# fonte-tensao-ajustavel.net
KiCad netlist of a schematic drawn in EAGLE
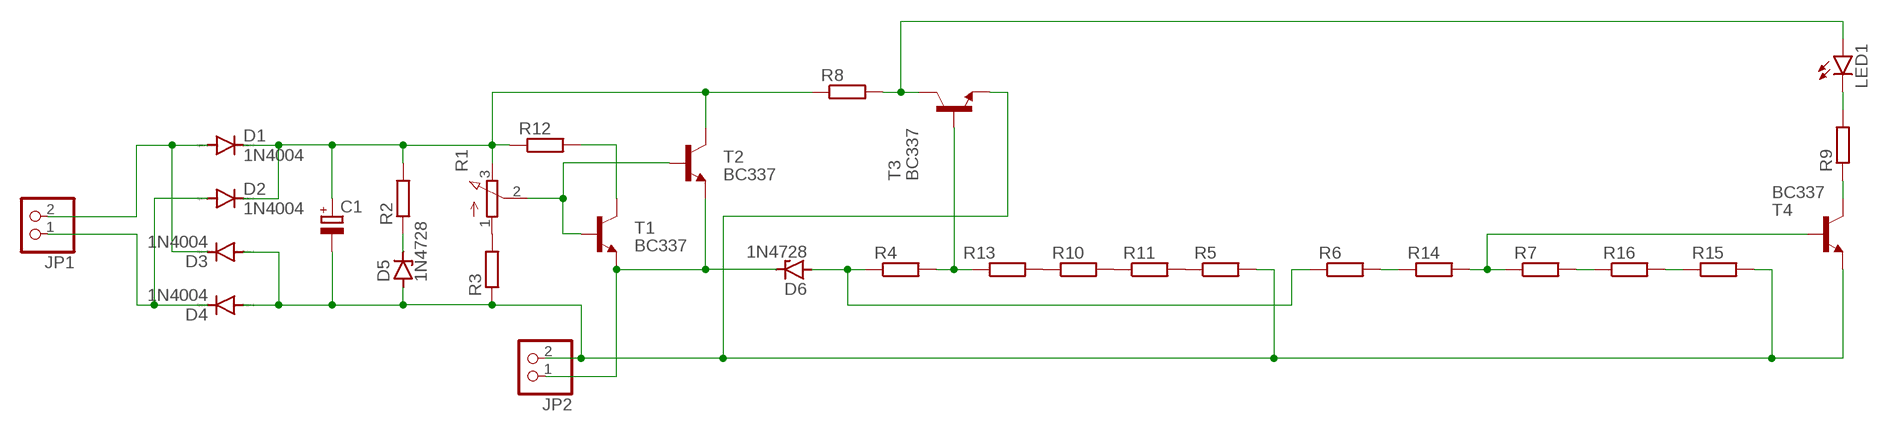
[diagram p0: schematic, sheet 1]

(export (version "E")
  (design (tool "Eeschema 10.0.6"))
  (components
    (comp (ref "C1")
      (value "CPOL-EUE5-10.5")
      (footprint "eagle-import:E5-10,5")
      (libsource (lib "eagle-import") (part "CPOL-EUE5-10.5"))
    )
    (comp (ref "D1")
      (value "1N4004")
      (footprint "eagle-import:DO41-10")
      (libsource (lib "eagle-import") (part "1N4004"))
    )
    (comp (ref "D2")
      (value "1N4004")
      (footprint "eagle-import:DO41-10")
      (libsource (lib "eagle-import") (part "1N4004"))
    )
    (comp (ref "D3")
      (value "1N4004")
      (footprint "eagle-import:DO41-10")
      (libsource (lib "eagle-import") (part "1N4004"))
    )
    (comp (ref "D4")
      (value "1N4004")
      (footprint "eagle-import:DO41-10")
      (libsource (lib "eagle-import") (part "1N4004"))
    )
    (comp (ref "D5")
      (value "1N4728")
      (footprint "eagle-import:DO41Z10")
      (libsource (lib "eagle-import") (part "1N4728"))
    )
    (comp (ref "D6")
      (value "1N4728")
      (footprint "eagle-import:DO41Z10")
      (libsource (lib "eagle-import") (part "1N4728"))
    )
    (comp (ref "JP1")
      (value "PINHD-1X2")
      (footprint "eagle-import:1X02")
      (libsource (lib "eagle-import") (part "PINHD-1X2"))
    )
    (comp (ref "JP2")
      (value "PINHD-1X2")
      (footprint "eagle-import:1X02")
      (libsource (lib "eagle-import") (part "PINHD-1X2"))
    )
    (comp (ref "LED1")
      (value "LED5MM")
      (footprint "eagle-import:LED5MM")
      (libsource (lib "eagle-import") (part "LED5MM"))
    )
    (comp (ref "R1")
      (value "3RP/1610N")
      (footprint "eagle-import:3RP_1610N")
      (libsource (lib "eagle-import") (part "3RP/1610N"))
    )
    (comp (ref "R2")
      (value "R-EU_0204/7")
      (footprint "eagle-import:0204_7")
      (libsource (lib "eagle-import") (part "R-EU_0204/7"))
    )
    (comp (ref "R3")
      (value "R-EU_0204/7")
      (footprint "eagle-import:0204_7")
      (libsource (lib "eagle-import") (part "R-EU_0204/7"))
    )
    (comp (ref "R4")
      (value "R-EU_0204/7")
      (footprint "eagle-import:0204_7")
      (libsource (lib "eagle-import") (part "R-EU_0204/7"))
    )
    (comp (ref "R5")
      (value "R-EU_0204/7")
      (footprint "eagle-import:0204_7")
      (libsource (lib "eagle-import") (part "R-EU_0204/7"))
    )
    (comp (ref "R6")
      (value "R-EU_0204/7")
      (footprint "eagle-import:0204_7")
      (libsource (lib "eagle-import") (part "R-EU_0204/7"))
    )
    (comp (ref "R7")
      (value "R-EU_0204/7")
      (footprint "eagle-import:0204_7")
      (libsource (lib "eagle-import") (part "R-EU_0204/7"))
    )
    (comp (ref "R8")
      (value "R-EU_0204/7")
      (footprint "eagle-import:0204_7")
      (libsource (lib "eagle-import") (part "R-EU_0204/7"))
    )
    (comp (ref "R9")
      (value "R-EU_0204/7")
      (footprint "eagle-import:0204_7")
      (libsource (lib "eagle-import") (part "R-EU_0204/7"))
    )
    (comp (ref "R10")
      (value "R-EU_0204/7")
      (footprint "eagle-import:0204_7")
      (libsource (lib "eagle-import") (part "R-EU_0204/7"))
    )
    (comp (ref "R11")
      (value "R-EU_0204/7")
      (footprint "eagle-import:0204_7")
      (libsource (lib "eagle-import") (part "R-EU_0204/7"))
    )
    (comp (ref "R12")
      (value "R-EU_0414/15")
      (footprint "eagle-import:0414_15")
      (libsource (lib "eagle-import") (part "R-EU_0414/15"))
    )
    (comp (ref "R13")
      (value "R-EU_0204/7")
      (footprint "eagle-import:0204_7")
      (libsource (lib "eagle-import") (part "R-EU_0204/7"))
    )
    (comp (ref "R14")
      (value "R-EU_0204/7")
      (footprint "eagle-import:0204_7")
      (libsource (lib "eagle-import") (part "R-EU_0204/7"))
    )
    (comp (ref "R15")
      (value "R-EU_0204/7")
      (footprint "eagle-import:0204_7")
      (libsource (lib "eagle-import") (part "R-EU_0204/7"))
    )
    (comp (ref "R16")
      (value "R-EU_0204/7")
      (footprint "eagle-import:0204_7")
      (libsource (lib "eagle-import") (part "R-EU_0204/7"))
    )
    (comp (ref "T1")
      (value "BC337")
      (footprint "eagle-import:TO92")
      (libsource (lib "eagle-import") (part "BC337"))
    )
    (comp (ref "T2")
      (value "BC337")
      (footprint "eagle-import:TO92")
      (libsource (lib "eagle-import") (part "BC337"))
    )
    (comp (ref "T3")
      (value "BC337")
      (footprint "eagle-import:TO92")
      (libsource (lib "eagle-import") (part "BC337"))
    )
    (comp (ref "T4")
      (value "BC337")
      (footprint "eagle-import:TO92")
      (libsource (lib "eagle-import") (part "BC337"))
    )
  )
  (nets
    (net (code "1") (name "Net-(D1-PadA)") (class "Default")
      (node (ref "D1") (pin "A") (pinfunction "A_A") (pintype "passive"))
      (node (ref "D3") (pin "C") (pinfunction "C_C") (pintype "passive"))
      (node (ref "JP1") (pin "2") (pinfunction "2_2") (pintype "passive"))
    )
    (net (code "2") (name "Net-(D2-PadA)") (class "Default")
      (node (ref "D2") (pin "A") (pinfunction "A_A") (pintype "passive"))
      (node (ref "D4") (pin "C") (pinfunction "C_C") (pintype "passive"))
      (node (ref "JP1") (pin "1") (pinfunction "1_1") (pintype "passive"))
    )
    (net (code "3") (name "Net-(D5-PadC)") (class "Default")
      (node (ref "D5") (pin "C") (pinfunction "C_C") (pintype "passive"))
      (node (ref "R2") (pin "1") (pinfunction "1_1") (pintype "passive"))
    )
    (net (code "4") (name "Net-(D6-PadA)") (class "Default")
      (node (ref "D6") (pin "A") (pinfunction "A_A") (pintype "passive"))
      (node (ref "R4") (pin "1") (pinfunction "1_1") (pintype "passive"))
      (node (ref "R6") (pin "1") (pinfunction "1_1") (pintype "passive"))
    )
    (net (code "5") (name "Net-(LED1-C)") (class "Default")
      (node (ref "LED1") (pin "K") (pinfunction "C_K") (pintype "passive"))
      (node (ref "R9") (pin "2") (pinfunction "2_2") (pintype "passive"))
    )
    (net (code "6") (name "Net-(R1-A)") (class "Default")
      (node (ref "R1") (pin "1") (pinfunction "A_1") (pintype "passive"))
      (node (ref "R3") (pin "2") (pinfunction "2_2") (pintype "passive"))
    )
    (net (code "7") (name "Net-(R1-E)") (class "Default")
      (node (ref "C1") (pin "+") (pinfunction "+_+") (pintype "passive"))
      (node (ref "D1") (pin "C") (pinfunction "C_C") (pintype "passive"))
      (node (ref "D2") (pin "C") (pinfunction "C_C") (pintype "passive"))
      (node (ref "R1") (pin "3") (pinfunction "E_3") (pintype "passive"))
      (node (ref "R12") (pin "1") (pinfunction "1_1") (pintype "passive"))
      (node (ref "R2") (pin "2") (pinfunction "2_2") (pintype "passive"))
      (node (ref "R8") (pin "1") (pinfunction "1_1") (pintype "passive"))
      (node (ref "T2") (pin "3") (pinfunction "C_3") (pintype "passive"))
    )
    (net (code "8") (name "Net-(R1-S)") (class "Default")
      (node (ref "R1") (pin "2") (pinfunction "S_2") (pintype "passive"))
      (node (ref "T1") (pin "2") (pinfunction "B_2") (pintype "passive"))
      (node (ref "T2") (pin "2") (pinfunction "B_2") (pintype "passive"))
    )
    (net (code "9") (name "Net-(R10-Pad1)") (class "Default")
      (node (ref "R10") (pin "1") (pinfunction "1_1") (pintype "passive"))
      (node (ref "R13") (pin "2") (pinfunction "2_2") (pintype "passive"))
    )
    (net (code "10") (name "Net-(R10-Pad2)") (class "Default")
      (node (ref "R10") (pin "2") (pinfunction "2_2") (pintype "passive"))
      (node (ref "R11") (pin "1") (pinfunction "1_1") (pintype "passive"))
    )
    (net (code "11") (name "Net-(R11-Pad2)") (class "Default")
      (node (ref "R11") (pin "2") (pinfunction "2_2") (pintype "passive"))
      (node (ref "R5") (pin "1") (pinfunction "1_1") (pintype "passive"))
    )
    (net (code "12") (name "Net-(R14-Pad1)") (class "Default")
      (node (ref "R14") (pin "1") (pinfunction "1_1") (pintype "passive"))
      (node (ref "R6") (pin "2") (pinfunction "2_2") (pintype "passive"))
    )
    (net (code "13") (name "Net-(R15-Pad1)") (class "Default")
      (node (ref "R15") (pin "1") (pinfunction "1_1") (pintype "passive"))
      (node (ref "R16") (pin "2") (pinfunction "2_2") (pintype "passive"))
    )
    (net (code "14") (name "Net-(R16-Pad1)") (class "Default")
      (node (ref "R16") (pin "1") (pinfunction "1_1") (pintype "passive"))
      (node (ref "R7") (pin "2") (pinfunction "2_2") (pintype "passive"))
    )
    (net (code "15") (name "Net-(T1-C)") (class "Default")
      (node (ref "R12") (pin "2") (pinfunction "2_2") (pintype "passive"))
      (node (ref "T1") (pin "3") (pinfunction "C_3") (pintype "passive"))
    )
    (net (code "16") (name "Net-(T1-E)") (class "Default")
      (node (ref "D6") (pin "C") (pinfunction "C_C") (pintype "passive"))
      (node (ref "JP2") (pin "1") (pinfunction "1_1") (pintype "passive"))
      (node (ref "T1") (pin "1") (pinfunction "E_1") (pintype "passive"))
      (node (ref "T2") (pin "1") (pinfunction "E_1") (pintype "passive"))
    )
    (net (code "17") (name "Net-(T3-B)") (class "Default")
      (node (ref "R13") (pin "1") (pinfunction "1_1") (pintype "passive"))
      (node (ref "R4") (pin "2") (pinfunction "2_2") (pintype "passive"))
      (node (ref "T3") (pin "2") (pinfunction "B_2") (pintype "passive"))
    )
    (net (code "18") (name "Net-(T3-C)") (class "Default")
      (node (ref "LED1") (pin "A") (pinfunction "A_A") (pintype "passive"))
      (node (ref "R8") (pin "2") (pinfunction "2_2") (pintype "passive"))
      (node (ref "T3") (pin "3") (pinfunction "C_3") (pintype "passive"))
    )
    (net (code "19") (name "Net-(T3-E)") (class "Default")
      (node (ref "C1") (pin "-") (pinfunction "-_-") (pintype "passive"))
      (node (ref "D3") (pin "A") (pinfunction "A_A") (pintype "passive"))
      (node (ref "D4") (pin "A") (pinfunction "A_A") (pintype "passive"))
      (node (ref "D5") (pin "A") (pinfunction "A_A") (pintype "passive"))
      (node (ref "JP2") (pin "2") (pinfunction "2_2") (pintype "passive"))
      (node (ref "R15") (pin "2") (pinfunction "2_2") (pintype "passive"))
      (node (ref "R3") (pin "1") (pinfunction "1_1") (pintype "passive"))
      (node (ref "R5") (pin "2") (pinfunction "2_2") (pintype "passive"))
      (node (ref "T3") (pin "1") (pinfunction "E_1") (pintype "passive"))
      (node (ref "T4") (pin "1") (pinfunction "E_1") (pintype "passive"))
    )
    (net (code "20") (name "Net-(T4-B)") (class "Default")
      (node (ref "R14") (pin "2") (pinfunction "2_2") (pintype "passive"))
      (node (ref "R7") (pin "1") (pinfunction "1_1") (pintype "passive"))
      (node (ref "T4") (pin "2") (pinfunction "B_2") (pintype "passive"))
    )
    (net (code "21") (name "Net-(T4-C)") (class "Default")
      (node (ref "R9") (pin "1") (pinfunction "1_1") (pintype "passive"))
      (node (ref "T4") (pin "3") (pinfunction "C_3") (pintype "passive"))
    )
  )
)
